# B204B.net
KiCad netlist of a schematic drawn in EAGLE
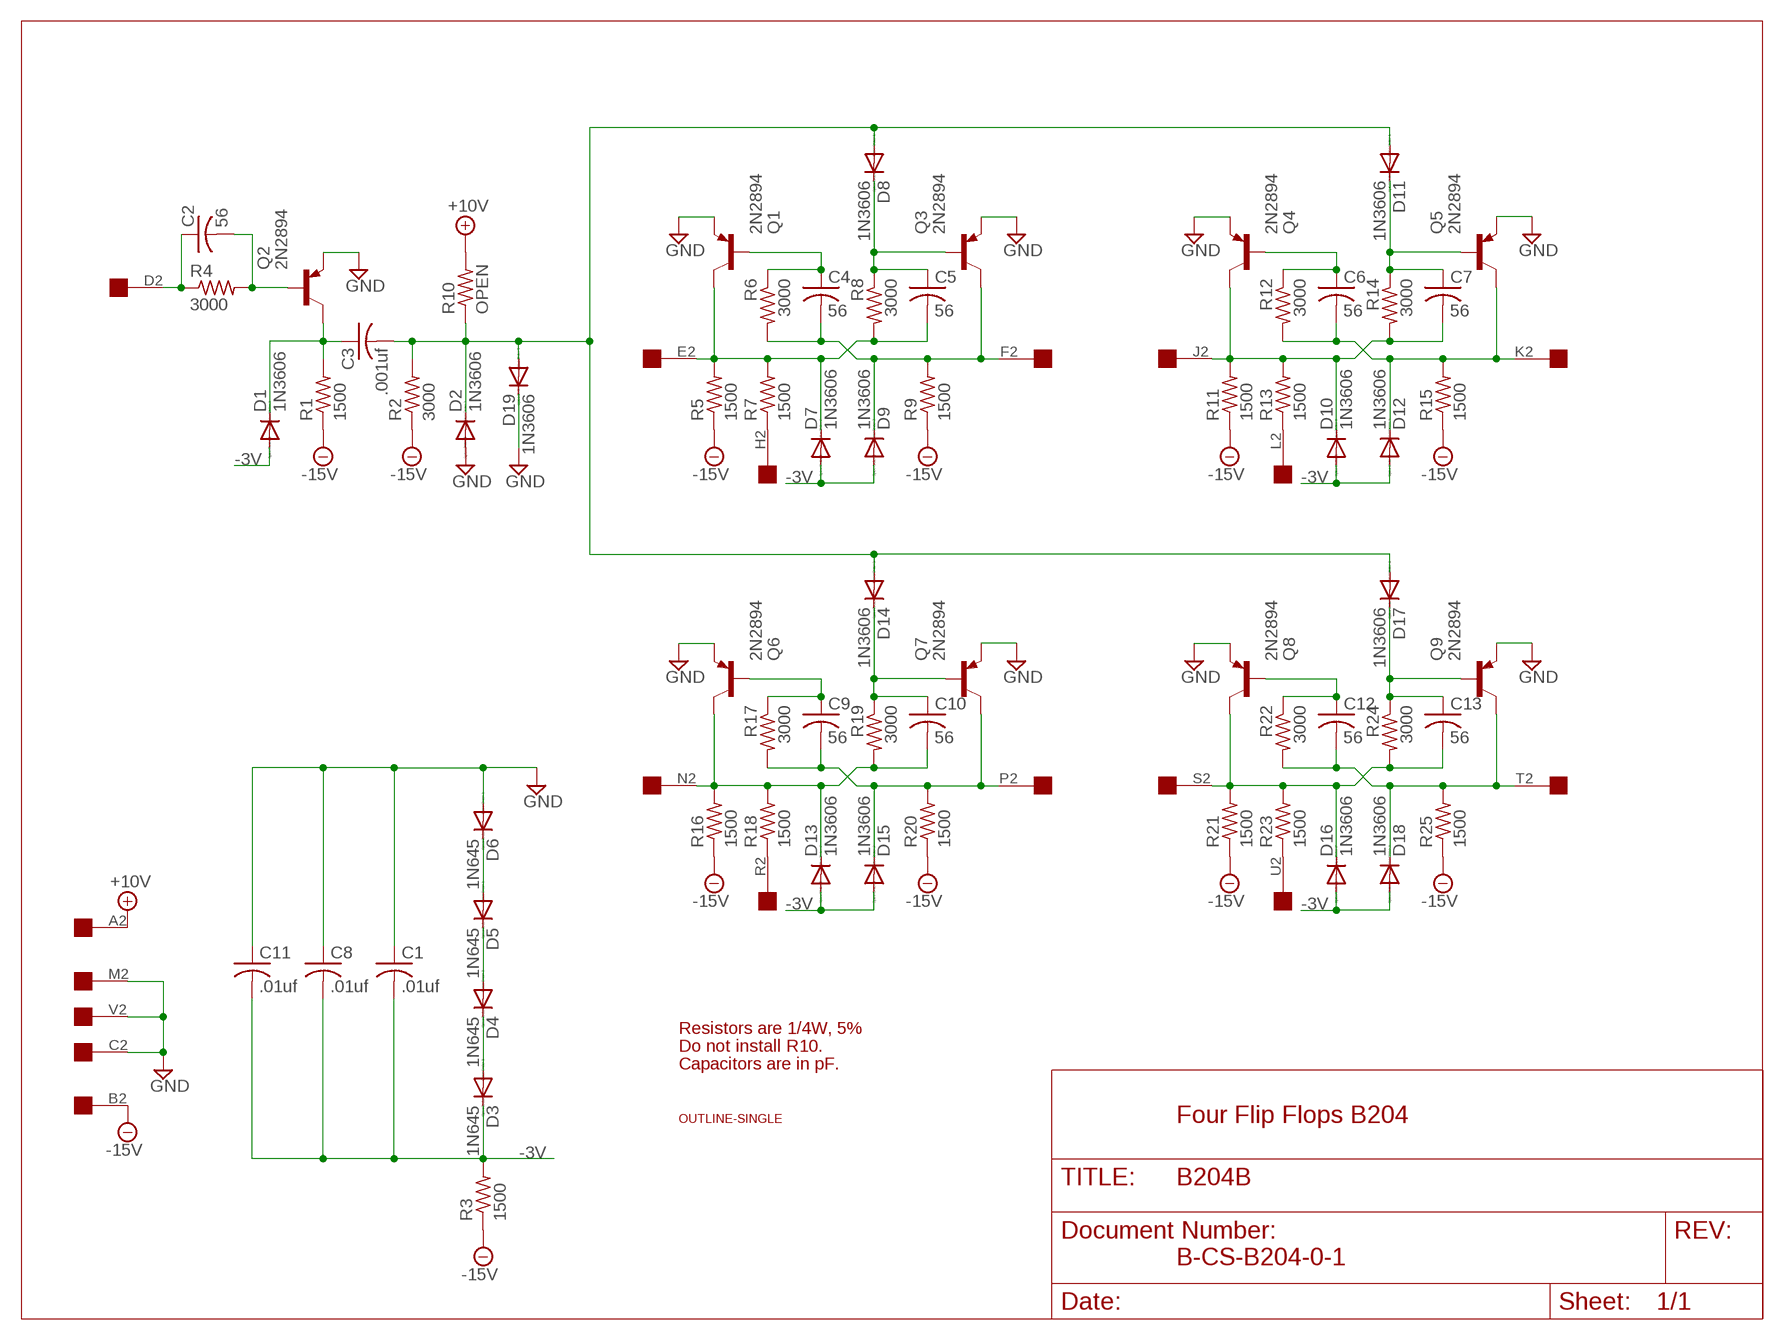
[diagram p0: schematic, sheet 1]

(export (version "E")
  (design (tool "Eeschema 10.0.6"))
  (components
    (comp (ref "C1")
      (value ".01uf")
      (footprint "eagle-import:C050-025X075")
      (libsource (lib "eagle-import") (part "C-US050-025X075"))
    )
    (comp (ref "C2")
      (value "56")
      (footprint "eagle-import:C075-032X103")
      (libsource (lib "eagle-import") (part "C-US075-032X103"))
    )
    (comp (ref "C3")
      (value ".001uf")
      (footprint "eagle-import:C050-025X075")
      (libsource (lib "eagle-import") (part "C-US050-025X075"))
    )
    (comp (ref "C4")
      (value "56")
      (footprint "eagle-import:C075-032X103")
      (libsource (lib "eagle-import") (part "C-US075-032X103"))
    )
    (comp (ref "C5")
      (value "56")
      (footprint "eagle-import:C075-032X103")
      (libsource (lib "eagle-import") (part "C-US075-032X103"))
    )
    (comp (ref "C6")
      (value "56")
      (footprint "eagle-import:C075-032X103")
      (libsource (lib "eagle-import") (part "C-US075-032X103"))
    )
    (comp (ref "C7")
      (value "56")
      (footprint "eagle-import:C075-032X103")
      (libsource (lib "eagle-import") (part "C-US075-032X103"))
    )
    (comp (ref "C8")
      (value ".01uf")
      (footprint "eagle-import:C050-025X075")
      (libsource (lib "eagle-import") (part "C-US050-025X075"))
    )
    (comp (ref "C9")
      (value "56")
      (footprint "eagle-import:C075-032X103")
      (libsource (lib "eagle-import") (part "C-US075-032X103"))
    )
    (comp (ref "C10")
      (value "56")
      (footprint "eagle-import:C075-032X103")
      (libsource (lib "eagle-import") (part "C-US075-032X103"))
    )
    (comp (ref "C11")
      (value ".01uf")
      (footprint "eagle-import:C050-025X075")
      (libsource (lib "eagle-import") (part "C-US050-025X075"))
    )
    (comp (ref "C12")
      (value "56")
      (footprint "eagle-import:C075-032X103")
      (libsource (lib "eagle-import") (part "C-US075-032X103"))
    )
    (comp (ref "C13")
      (value "56")
      (footprint "eagle-import:C075-032X103")
      (libsource (lib "eagle-import") (part "C-US075-032X103"))
    )
    (comp (ref "D1")
      (value "1N3606")
      (footprint "eagle-import:DO35-10")
      (libsource (lib "eagle-import") (part "1N4148DO35-10"))
    )
    (comp (ref "D2")
      (value "1N3606")
      (footprint "eagle-import:DO35-10")
      (libsource (lib "eagle-import") (part "1N4148DO35-10"))
    )
    (comp (ref "D3")
      (value "1N645")
      (footprint "eagle-import:DO35-10")
      (libsource (lib "eagle-import") (part "1N4148DO35-10"))
    )
    (comp (ref "D4")
      (value "1N645")
      (footprint "eagle-import:DO35-10")
      (libsource (lib "eagle-import") (part "1N4148DO35-10"))
    )
    (comp (ref "D5")
      (value "1N645")
      (footprint "eagle-import:DO35-10")
      (libsource (lib "eagle-import") (part "1N4148DO35-10"))
    )
    (comp (ref "D6")
      (value "1N645")
      (footprint "eagle-import:DO35-10")
      (libsource (lib "eagle-import") (part "1N4148DO35-10"))
    )
    (comp (ref "D7")
      (value "1N3606")
      (footprint "eagle-import:DO35-10")
      (libsource (lib "eagle-import") (part "1N4148DO35-10"))
    )
    (comp (ref "D8")
      (value "1N3606")
      (footprint "eagle-import:DO35-10")
      (libsource (lib "eagle-import") (part "1N4148DO35-10"))
    )
    (comp (ref "D9")
      (value "1N3606")
      (footprint "eagle-import:DO35-10")
      (libsource (lib "eagle-import") (part "1N4148DO35-10"))
    )
    (comp (ref "D10")
      (value "1N3606")
      (footprint "eagle-import:DO35-10")
      (libsource (lib "eagle-import") (part "1N4148DO35-10"))
    )
    (comp (ref "D11")
      (value "1N3606")
      (footprint "eagle-import:DO35-10")
      (libsource (lib "eagle-import") (part "1N4148DO35-10"))
    )
    (comp (ref "D12")
      (value "1N3606")
      (footprint "eagle-import:DO35-10")
      (libsource (lib "eagle-import") (part "1N4148DO35-10"))
    )
    (comp (ref "D13")
      (value "1N3606")
      (footprint "eagle-import:DO35-10")
      (libsource (lib "eagle-import") (part "1N4148DO35-10"))
    )
    (comp (ref "D14")
      (value "1N3606")
      (footprint "eagle-import:DO35-10")
      (libsource (lib "eagle-import") (part "1N4148DO35-10"))
    )
    (comp (ref "D15")
      (value "1N3606")
      (footprint "eagle-import:DO35-10")
      (libsource (lib "eagle-import") (part "1N4148DO35-10"))
    )
    (comp (ref "D16")
      (value "1N3606")
      (footprint "eagle-import:DO35-10")
      (libsource (lib "eagle-import") (part "1N4148DO35-10"))
    )
    (comp (ref "D17")
      (value "1N3606")
      (footprint "eagle-import:DO35-10")
      (libsource (lib "eagle-import") (part "1N4148DO35-10"))
    )
    (comp (ref "D18")
      (value "1N3606")
      (footprint "eagle-import:DO35-10")
      (libsource (lib "eagle-import") (part "1N4148DO35-10"))
    )
    (comp (ref "D19")
      (value "1N3606")
      (footprint "eagle-import:DO35-10")
      (libsource (lib "eagle-import") (part "1N4148DO35-10"))
    )
    (comp (ref "Q1")
      (value "2N2894")
      (footprint "eagle-import:TO39")
      (libsource (lib "eagle-import") (part "2N3637"))
    )
    (comp (ref "Q2")
      (value "2N2894")
      (footprint "eagle-import:TO39")
      (libsource (lib "eagle-import") (part "2N3637"))
    )
    (comp (ref "Q3")
      (value "2N2894")
      (footprint "eagle-import:TO39")
      (libsource (lib "eagle-import") (part "2N3637"))
    )
    (comp (ref "Q4")
      (value "2N2894")
      (footprint "eagle-import:TO39")
      (libsource (lib "eagle-import") (part "2N3637"))
    )
    (comp (ref "Q5")
      (value "2N2894")
      (footprint "eagle-import:TO39")
      (libsource (lib "eagle-import") (part "2N3637"))
    )
    (comp (ref "Q6")
      (value "2N2894")
      (footprint "eagle-import:TO39")
      (libsource (lib "eagle-import") (part "2N3637"))
    )
    (comp (ref "Q7")
      (value "2N2894")
      (footprint "eagle-import:TO39")
      (libsource (lib "eagle-import") (part "2N3637"))
    )
    (comp (ref "Q8")
      (value "2N2894")
      (footprint "eagle-import:TO39")
      (libsource (lib "eagle-import") (part "2N3637"))
    )
    (comp (ref "Q9")
      (value "2N2894")
      (footprint "eagle-import:TO39")
      (libsource (lib "eagle-import") (part "2N3637"))
    )
    (comp (ref "R1")
      (value "1500")
      (footprint "eagle-import:0207_10")
      (libsource (lib "eagle-import") (part "R-US_0207/10"))
    )
    (comp (ref "R2")
      (value "3000")
      (footprint "eagle-import:0207_10")
      (libsource (lib "eagle-import") (part "R-US_0207/10"))
    )
    (comp (ref "R3")
      (value "1500")
      (footprint "eagle-import:0207_10")
      (libsource (lib "eagle-import") (part "R-US_0207/10"))
    )
    (comp (ref "R4")
      (value "3000")
      (footprint "eagle-import:0207_10")
      (libsource (lib "eagle-import") (part "R-US_0207/10"))
    )
    (comp (ref "R5")
      (value "1500")
      (footprint "eagle-import:0207_10")
      (libsource (lib "eagle-import") (part "R-US_0207/10"))
    )
    (comp (ref "R6")
      (value "3000")
      (footprint "eagle-import:0207_10")
      (libsource (lib "eagle-import") (part "R-US_0207/10"))
    )
    (comp (ref "R7")
      (value "1500")
      (footprint "eagle-import:0207_10")
      (libsource (lib "eagle-import") (part "R-US_0207/10"))
    )
    (comp (ref "R8")
      (value "3000")
      (footprint "eagle-import:0207_10")
      (libsource (lib "eagle-import") (part "R-US_0207/10"))
    )
    (comp (ref "R9")
      (value "1500")
      (footprint "eagle-import:0207_10")
      (libsource (lib "eagle-import") (part "R-US_0207/10"))
    )
    (comp (ref "R10")
      (value "OPEN")
      (footprint "eagle-import:0207_10")
      (libsource (lib "eagle-import") (part "R-US_0207/10"))
    )
    (comp (ref "R11")
      (value "1500")
      (footprint "eagle-import:0207_10")
      (libsource (lib "eagle-import") (part "R-US_0207/10"))
    )
    (comp (ref "R12")
      (value "3000")
      (footprint "eagle-import:0207_10")
      (libsource (lib "eagle-import") (part "R-US_0207/10"))
    )
    (comp (ref "R13")
      (value "1500")
      (footprint "eagle-import:0207_10")
      (libsource (lib "eagle-import") (part "R-US_0207/10"))
    )
    (comp (ref "R14")
      (value "3000")
      (footprint "eagle-import:0207_10")
      (libsource (lib "eagle-import") (part "R-US_0207/10"))
    )
    (comp (ref "R15")
      (value "1500")
      (footprint "eagle-import:0207_10")
      (libsource (lib "eagle-import") (part "R-US_0207/10"))
    )
    (comp (ref "R16")
      (value "1500")
      (footprint "eagle-import:0207_10")
      (libsource (lib "eagle-import") (part "R-US_0207/10"))
    )
    (comp (ref "R17")
      (value "3000")
      (footprint "eagle-import:0207_10")
      (libsource (lib "eagle-import") (part "R-US_0207/10"))
    )
    (comp (ref "R18")
      (value "1500")
      (footprint "eagle-import:0207_10")
      (libsource (lib "eagle-import") (part "R-US_0207/10"))
    )
    (comp (ref "R19")
      (value "3000")
      (footprint "eagle-import:0207_10")
      (libsource (lib "eagle-import") (part "R-US_0207/10"))
    )
    (comp (ref "R20")
      (value "1500")
      (footprint "eagle-import:0207_10")
      (libsource (lib "eagle-import") (part "R-US_0207/10"))
    )
    (comp (ref "R21")
      (value "1500")
      (footprint "eagle-import:0207_10")
      (libsource (lib "eagle-import") (part "R-US_0207/10"))
    )
    (comp (ref "R22")
      (value "3000")
      (footprint "eagle-import:0207_10")
      (libsource (lib "eagle-import") (part "R-US_0207/10"))
    )
    (comp (ref "R23")
      (value "1500")
      (footprint "eagle-import:0207_10")
      (libsource (lib "eagle-import") (part "R-US_0207/10"))
    )
    (comp (ref "R24")
      (value "3000")
      (footprint "eagle-import:0207_10")
      (libsource (lib "eagle-import") (part "R-US_0207/10"))
    )
    (comp (ref "R25")
      (value "1500")
      (footprint "eagle-import:0207_10")
      (libsource (lib "eagle-import") (part "R-US_0207/10"))
    )
    (comp (ref "U$1")
      (value "OUTLINE-SINGLE")
      (footprint "eagle-import:SINGLE")
      (libsource (lib "eagle-import") (part "OUTLINE-SINGLE"))
    )
    (comp (ref "U$2")
      (value "EDGE-1")
      (footprint "eagle-import:EDGE-CON1")
      (libsource (lib "eagle-import") (part "EDGE-1"))
    )
  )
  (nets
    (net (code "1") (name "+10V") (class "Default")
      (node (ref "R10") (pin "2") (pinfunction "2_2") (pintype "passive"))
      (node (ref "U$2") (pin "A2") (pinfunction "1_A2") (pintype "bidirectional"))
    )
    (net (code "2") (name "-15V") (class "Default")
      (node (ref "R1") (pin "1") (pinfunction "1_1") (pintype "passive"))
      (node (ref "R11") (pin "1") (pinfunction "1_1") (pintype "passive"))
      (node (ref "R15") (pin "1") (pinfunction "1_1") (pintype "passive"))
      (node (ref "R16") (pin "1") (pinfunction "1_1") (pintype "passive"))
      (node (ref "R2") (pin "1") (pinfunction "1_1") (pintype "passive"))
      (node (ref "R20") (pin "1") (pinfunction "1_1") (pintype "passive"))
      (node (ref "R21") (pin "1") (pinfunction "1_1") (pintype "passive"))
      (node (ref "R25") (pin "1") (pinfunction "1_1") (pintype "passive"))
      (node (ref "R3") (pin "1") (pinfunction "1_1") (pintype "passive"))
      (node (ref "R5") (pin "1") (pinfunction "1_1") (pintype "passive"))
      (node (ref "R9") (pin "1") (pinfunction "1_1") (pintype "passive"))
      (node (ref "U$2") (pin "B2") (pinfunction "1_B2") (pintype "bidirectional"))
    )
    (net (code "3") (name "/-3V") (class "Default")
      (node (ref "C1") (pin "2") (pinfunction "2_2") (pintype "passive"))
      (node (ref "C11") (pin "2") (pinfunction "2_2") (pintype "passive"))
      (node (ref "C8") (pin "2") (pinfunction "2_2") (pintype "passive"))
      (node (ref "D1") (pin "A") (pinfunction "A_A") (pintype "passive"))
      (node (ref "D10") (pin "A") (pinfunction "A_A") (pintype "passive"))
      (node (ref "D12") (pin "A") (pinfunction "A_A") (pintype "passive"))
      (node (ref "D13") (pin "A") (pinfunction "A_A") (pintype "passive"))
      (node (ref "D15") (pin "A") (pinfunction "A_A") (pintype "passive"))
      (node (ref "D16") (pin "A") (pinfunction "A_A") (pintype "passive"))
      (node (ref "D18") (pin "A") (pinfunction "A_A") (pintype "passive"))
      (node (ref "D3") (pin "C") (pinfunction "C_C") (pintype "passive"))
      (node (ref "D7") (pin "A") (pinfunction "A_A") (pintype "passive"))
      (node (ref "D9") (pin "A") (pinfunction "A_A") (pintype "passive"))
      (node (ref "R3") (pin "2") (pinfunction "2_2") (pintype "passive"))
    )
    (net (code "4") (name "GND") (class "Default")
      (node (ref "C1") (pin "1") (pinfunction "1_1") (pintype "passive"))
      (node (ref "C11") (pin "1") (pinfunction "1_1") (pintype "passive"))
      (node (ref "C8") (pin "1") (pinfunction "1_1") (pintype "passive"))
      (node (ref "D19") (pin "C") (pinfunction "C_C") (pintype "passive"))
      (node (ref "D2") (pin "A") (pinfunction "A_A") (pintype "passive"))
      (node (ref "D6") (pin "A") (pinfunction "A_A") (pintype "passive"))
      (node (ref "Q1") (pin "1") (pinfunction "E_1") (pintype "passive"))
      (node (ref "Q2") (pin "1") (pinfunction "E_1") (pintype "passive"))
      (node (ref "Q3") (pin "1") (pinfunction "E_1") (pintype "passive"))
      (node (ref "Q4") (pin "1") (pinfunction "E_1") (pintype "passive"))
      (node (ref "Q5") (pin "1") (pinfunction "E_1") (pintype "passive"))
      (node (ref "Q6") (pin "1") (pinfunction "E_1") (pintype "passive"))
      (node (ref "Q7") (pin "1") (pinfunction "E_1") (pintype "passive"))
      (node (ref "Q8") (pin "1") (pinfunction "E_1") (pintype "passive"))
      (node (ref "Q9") (pin "1") (pinfunction "E_1") (pintype "passive"))
      (node (ref "U$2") (pin "C2") (pinfunction "1_C2") (pintype "bidirectional"))
      (node (ref "U$2") (pin "M2") (pinfunction "1_M2") (pintype "bidirectional"))
      (node (ref "U$2") (pin "V2") (pinfunction "1_V2") (pintype "bidirectional"))
    )
    (net (code "5") (name "Net-(C3-Pad2)") (class "Default")
      (node (ref "C3") (pin "2") (pinfunction "2_2") (pintype "passive"))
      (node (ref "D11") (pin "A") (pinfunction "A_A") (pintype "passive"))
      (node (ref "D14") (pin "A") (pinfunction "A_A") (pintype "passive"))
      (node (ref "D17") (pin "A") (pinfunction "A_A") (pintype "passive"))
      (node (ref "D19") (pin "A") (pinfunction "A_A") (pintype "passive"))
      (node (ref "D2") (pin "C") (pinfunction "C_C") (pintype "passive"))
      (node (ref "D8") (pin "A") (pinfunction "A_A") (pintype "passive"))
      (node (ref "R10") (pin "1") (pinfunction "1_1") (pintype "passive"))
      (node (ref "R2") (pin "2") (pinfunction "2_2") (pintype "passive"))
    )
    (net (code "6") (name "Net-(D3-PadA)") (class "Default")
      (node (ref "D3") (pin "A") (pinfunction "A_A") (pintype "passive"))
      (node (ref "D4") (pin "C") (pinfunction "C_C") (pintype "passive"))
    )
    (net (code "7") (name "Net-(D4-PadA)") (class "Default")
      (node (ref "D4") (pin "A") (pinfunction "A_A") (pintype "passive"))
      (node (ref "D5") (pin "C") (pinfunction "C_C") (pintype "passive"))
    )
    (net (code "8") (name "Net-(D5-PadA)") (class "Default")
      (node (ref "D5") (pin "A") (pinfunction "A_A") (pintype "passive"))
      (node (ref "D6") (pin "C") (pinfunction "C_C") (pintype "passive"))
    )
    (net (code "9") (name "Net-(Q1-B)") (class "Default")
      (node (ref "C4") (pin "1") (pinfunction "1_1") (pintype "passive"))
      (node (ref "Q1") (pin "2") (pinfunction "B_2") (pintype "passive"))
      (node (ref "R6") (pin "1") (pinfunction "1_1") (pintype "passive"))
    )
    (net (code "10") (name "Net-(Q1-C)") (class "Default")
      (node (ref "C5") (pin "2") (pinfunction "2_2") (pintype "passive"))
      (node (ref "D7") (pin "C") (pinfunction "C_C") (pintype "passive"))
      (node (ref "Q1") (pin "3") (pinfunction "C_3") (pintype "passive"))
      (node (ref "R5") (pin "2") (pinfunction "2_2") (pintype "passive"))
      (node (ref "R7") (pin "2") (pinfunction "2_2") (pintype "passive"))
      (node (ref "R8") (pin "2") (pinfunction "2_2") (pintype "passive"))
      (node (ref "U$2") (pin "E2") (pinfunction "1_E2") (pintype "bidirectional"))
    )
    (net (code "11") (name "Net-(Q2-B)") (class "Default")
      (node (ref "C2") (pin "2") (pinfunction "2_2") (pintype "passive"))
      (node (ref "Q2") (pin "2") (pinfunction "B_2") (pintype "passive"))
      (node (ref "R4") (pin "2") (pinfunction "2_2") (pintype "passive"))
    )
    (net (code "12") (name "Net-(Q2-C)") (class "Default")
      (node (ref "C3") (pin "1") (pinfunction "1_1") (pintype "passive"))
      (node (ref "D1") (pin "C") (pinfunction "C_C") (pintype "passive"))
      (node (ref "Q2") (pin "3") (pinfunction "C_3") (pintype "passive"))
      (node (ref "R1") (pin "2") (pinfunction "2_2") (pintype "passive"))
    )
    (net (code "13") (name "Net-(Q3-B)") (class "Default")
      (node (ref "C5") (pin "1") (pinfunction "1_1") (pintype "passive"))
      (node (ref "D8") (pin "C") (pinfunction "C_C") (pintype "passive"))
      (node (ref "Q3") (pin "2") (pinfunction "B_2") (pintype "passive"))
      (node (ref "R8") (pin "1") (pinfunction "1_1") (pintype "passive"))
    )
    (net (code "14") (name "Net-(Q3-C)") (class "Default")
      (node (ref "C4") (pin "2") (pinfunction "2_2") (pintype "passive"))
      (node (ref "D9") (pin "C") (pinfunction "C_C") (pintype "passive"))
      (node (ref "Q3") (pin "3") (pinfunction "C_3") (pintype "passive"))
      (node (ref "R6") (pin "2") (pinfunction "2_2") (pintype "passive"))
      (node (ref "R9") (pin "2") (pinfunction "2_2") (pintype "passive"))
      (node (ref "U$2") (pin "F2") (pinfunction "1_F2") (pintype "bidirectional"))
    )
    (net (code "15") (name "Net-(Q4-B)") (class "Default")
      (node (ref "C6") (pin "1") (pinfunction "1_1") (pintype "passive"))
      (node (ref "Q4") (pin "2") (pinfunction "B_2") (pintype "passive"))
      (node (ref "R12") (pin "1") (pinfunction "1_1") (pintype "passive"))
    )
    (net (code "16") (name "Net-(Q4-C)") (class "Default")
      (node (ref "C7") (pin "2") (pinfunction "2_2") (pintype "passive"))
      (node (ref "D10") (pin "C") (pinfunction "C_C") (pintype "passive"))
      (node (ref "Q4") (pin "3") (pinfunction "C_3") (pintype "passive"))
      (node (ref "R11") (pin "2") (pinfunction "2_2") (pintype "passive"))
      (node (ref "R13") (pin "2") (pinfunction "2_2") (pintype "passive"))
      (node (ref "R14") (pin "2") (pinfunction "2_2") (pintype "passive"))
      (node (ref "U$2") (pin "J2") (pinfunction "1_J2") (pintype "bidirectional"))
    )
    (net (code "17") (name "Net-(Q5-B)") (class "Default")
      (node (ref "C7") (pin "1") (pinfunction "1_1") (pintype "passive"))
      (node (ref "D11") (pin "C") (pinfunction "C_C") (pintype "passive"))
      (node (ref "Q5") (pin "2") (pinfunction "B_2") (pintype "passive"))
      (node (ref "R14") (pin "1") (pinfunction "1_1") (pintype "passive"))
    )
    (net (code "18") (name "Net-(Q5-C)") (class "Default")
      (node (ref "C6") (pin "2") (pinfunction "2_2") (pintype "passive"))
      (node (ref "D12") (pin "C") (pinfunction "C_C") (pintype "passive"))
      (node (ref "Q5") (pin "3") (pinfunction "C_3") (pintype "passive"))
      (node (ref "R12") (pin "2") (pinfunction "2_2") (pintype "passive"))
      (node (ref "R15") (pin "2") (pinfunction "2_2") (pintype "passive"))
      (node (ref "U$2") (pin "K2") (pinfunction "1_K2") (pintype "bidirectional"))
    )
    (net (code "19") (name "Net-(Q6-B)") (class "Default")
      (node (ref "C9") (pin "1") (pinfunction "1_1") (pintype "passive"))
      (node (ref "Q6") (pin "2") (pinfunction "B_2") (pintype "passive"))
      (node (ref "R17") (pin "1") (pinfunction "1_1") (pintype "passive"))
    )
    (net (code "20") (name "Net-(Q6-C)") (class "Default")
      (node (ref "C10") (pin "2") (pinfunction "2_2") (pintype "passive"))
      (node (ref "D13") (pin "C") (pinfunction "C_C") (pintype "passive"))
      (node (ref "Q6") (pin "3") (pinfunction "C_3") (pintype "passive"))
      (node (ref "R16") (pin "2") (pinfunction "2_2") (pintype "passive"))
      (node (ref "R18") (pin "2") (pinfunction "2_2") (pintype "passive"))
      (node (ref "R19") (pin "2") (pinfunction "2_2") (pintype "passive"))
      (node (ref "U$2") (pin "N2") (pinfunction "1_N2") (pintype "bidirectional"))
    )
    (net (code "21") (name "Net-(Q7-B)") (class "Default")
      (node (ref "C10") (pin "1") (pinfunction "1_1") (pintype "passive"))
      (node (ref "D14") (pin "C") (pinfunction "C_C") (pintype "passive"))
      (node (ref "Q7") (pin "2") (pinfunction "B_2") (pintype "passive"))
      (node (ref "R19") (pin "1") (pinfunction "1_1") (pintype "passive"))
    )
    (net (code "22") (name "Net-(Q7-C)") (class "Default")
      (node (ref "C9") (pin "2") (pinfunction "2_2") (pintype "passive"))
      (node (ref "D15") (pin "C") (pinfunction "C_C") (pintype "passive"))
      (node (ref "Q7") (pin "3") (pinfunction "C_3") (pintype "passive"))
      (node (ref "R17") (pin "2") (pinfunction "2_2") (pintype "passive"))
      (node (ref "R20") (pin "2") (pinfunction "2_2") (pintype "passive"))
      (node (ref "U$2") (pin "P2") (pinfunction "1_P2") (pintype "bidirectional"))
    )
    (net (code "23") (name "Net-(Q8-B)") (class "Default")
      (node (ref "C12") (pin "1") (pinfunction "1_1") (pintype "passive"))
      (node (ref "Q8") (pin "2") (pinfunction "B_2") (pintype "passive"))
      (node (ref "R22") (pin "1") (pinfunction "1_1") (pintype "passive"))
    )
    (net (code "24") (name "Net-(Q8-C)") (class "Default")
      (node (ref "C13") (pin "2") (pinfunction "2_2") (pintype "passive"))
      (node (ref "D16") (pin "C") (pinfunction "C_C") (pintype "passive"))
      (node (ref "Q8") (pin "3") (pinfunction "C_3") (pintype "passive"))
      (node (ref "R21") (pin "2") (pinfunction "2_2") (pintype "passive"))
      (node (ref "R23") (pin "2") (pinfunction "2_2") (pintype "passive"))
      (node (ref "R24") (pin "2") (pinfunction "2_2") (pintype "passive"))
      (node (ref "U$2") (pin "S2") (pinfunction "1_S2") (pintype "bidirectional"))
    )
    (net (code "25") (name "Net-(Q9-B)") (class "Default")
      (node (ref "C13") (pin "1") (pinfunction "1_1") (pintype "passive"))
      (node (ref "D17") (pin "C") (pinfunction "C_C") (pintype "passive"))
      (node (ref "Q9") (pin "2") (pinfunction "B_2") (pintype "passive"))
      (node (ref "R24") (pin "1") (pinfunction "1_1") (pintype "passive"))
    )
    (net (code "26") (name "Net-(Q9-C)") (class "Default")
      (node (ref "C12") (pin "2") (pinfunction "2_2") (pintype "passive"))
      (node (ref "D18") (pin "C") (pinfunction "C_C") (pintype "passive"))
      (node (ref "Q9") (pin "3") (pinfunction "C_3") (pintype "passive"))
      (node (ref "R22") (pin "2") (pinfunction "2_2") (pintype "passive"))
      (node (ref "R25") (pin "2") (pinfunction "2_2") (pintype "passive"))
      (node (ref "U$2") (pin "T2") (pinfunction "1_T2") (pintype "bidirectional"))
    )
    (net (code "27") (name "Net-(U$2D-1)") (class "Default")
      (node (ref "C2") (pin "1") (pinfunction "1_1") (pintype "passive"))
      (node (ref "R4") (pin "1") (pinfunction "1_1") (pintype "passive"))
      (node (ref "U$2") (pin "D2") (pinfunction "1_D2") (pintype "bidirectional"))
    )
    (net (code "28") (name "Net-(U$2G-1)") (class "Default")
      (node (ref "R7") (pin "1") (pinfunction "1_1") (pintype "passive"))
      (node (ref "U$2") (pin "H2") (pinfunction "1_H2") (pintype "bidirectional"))
    )
    (net (code "29") (name "Net-(U$2J-1)") (class "Default")
      (node (ref "R13") (pin "1") (pinfunction "1_1") (pintype "passive"))
      (node (ref "U$2") (pin "L2") (pinfunction "1_L2") (pintype "bidirectional"))
    )
    (net (code "30") (name "Net-(U$2N-1)") (class "Default")
      (node (ref "R18") (pin "1") (pinfunction "1_1") (pintype "passive"))
      (node (ref "U$2") (pin "R2") (pinfunction "1_R2") (pintype "bidirectional"))
    )
    (net (code "31") (name "Net-(U$2Q-1)") (class "Default")
      (node (ref "R23") (pin "1") (pinfunction "1_1") (pintype "passive"))
      (node (ref "U$2") (pin "U2") (pinfunction "1_U2") (pintype "bidirectional"))
    )
  )
)
